# airball_sensor_board_v2.net
KiCad netlist of a schematic drawn in EAGLE
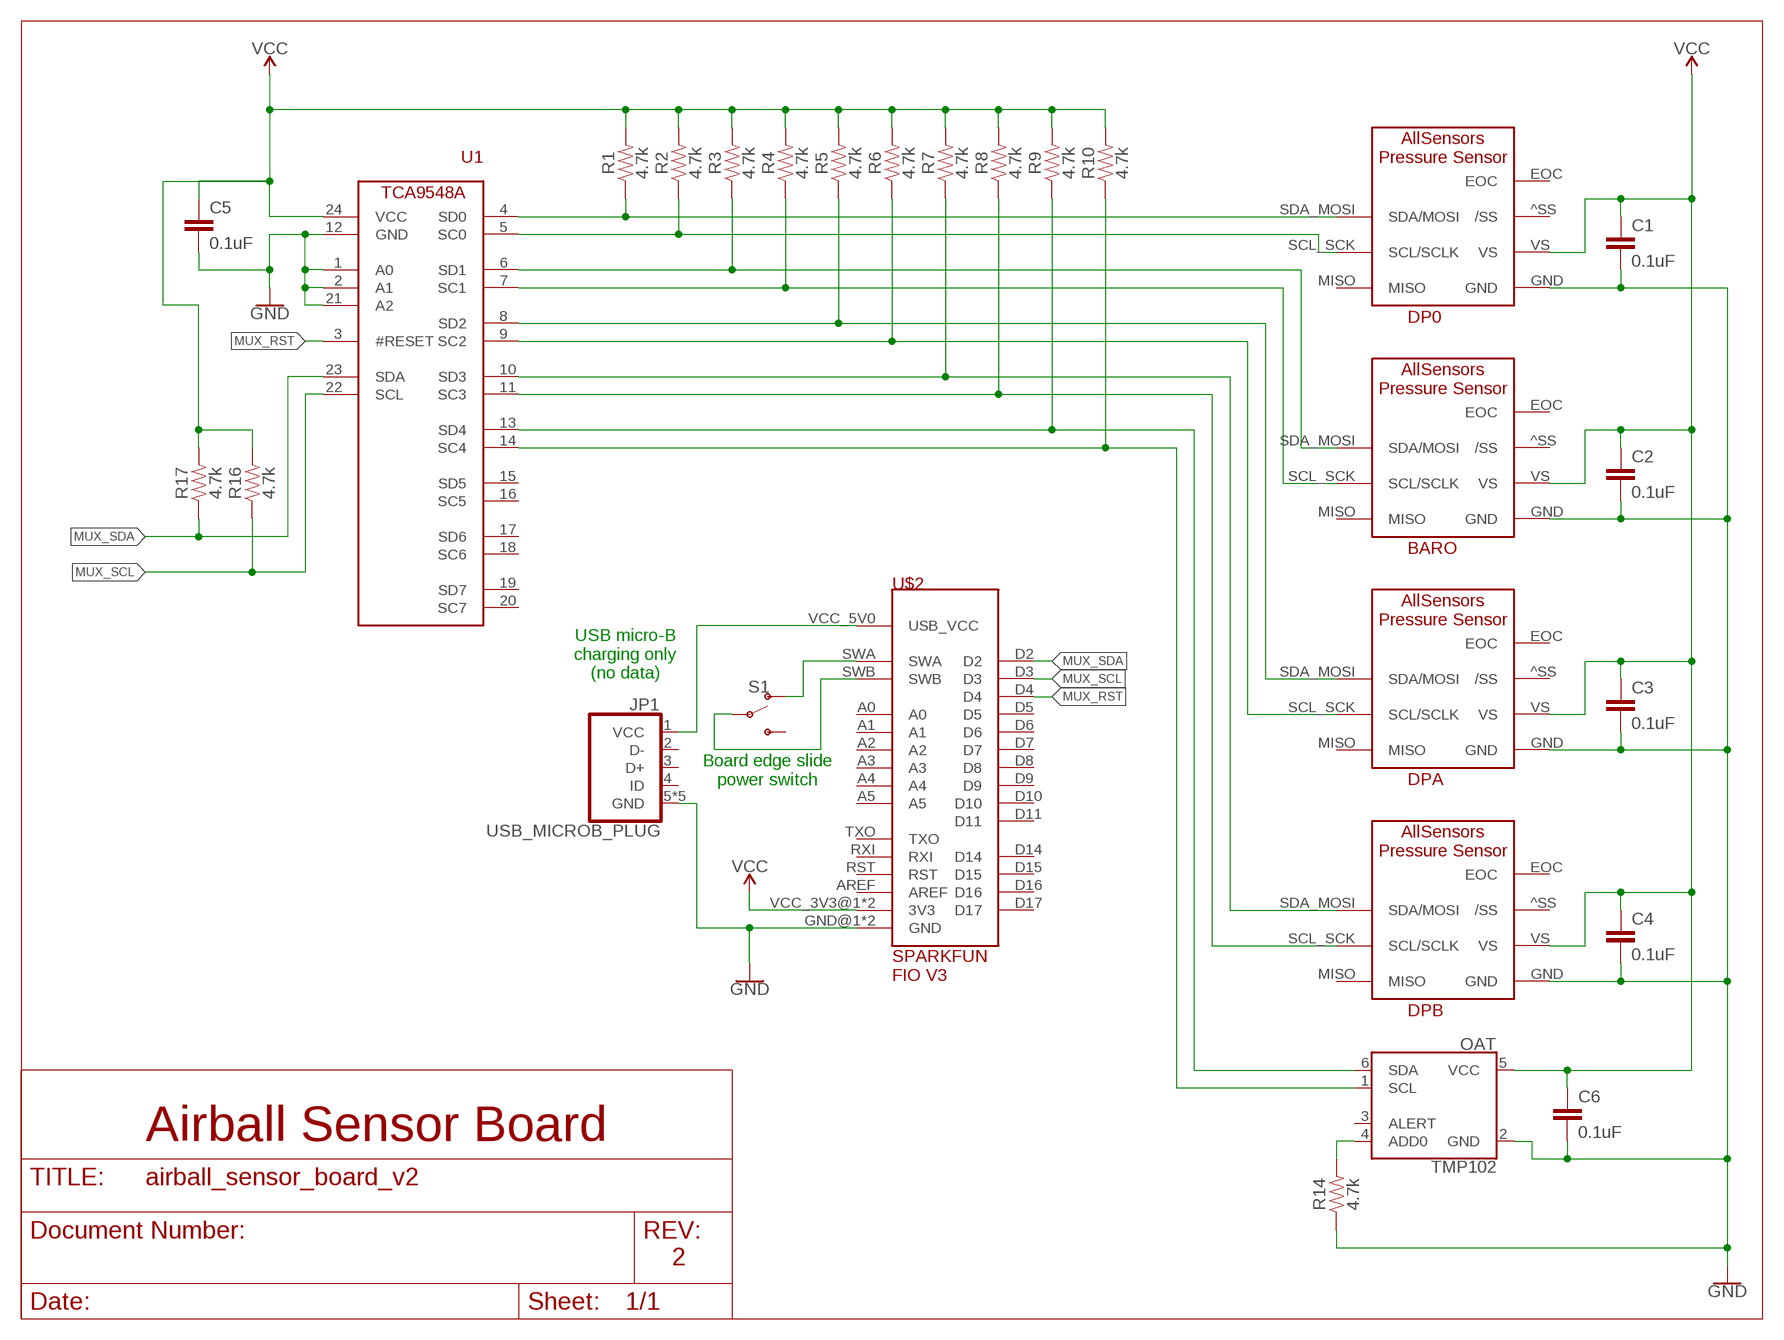
[diagram p0: schematic, sheet 1]

(export (version "E")
  (design (tool "Eeschema 10.0.6"))
  (components
    (comp (ref "BARO")
      (value "ALL_SENSORS_DLHR_E1ND")
      (footprint "eagle-import:ALL_SENSORS_E1BD_8PIN_THRU")
      (libsource (lib "eagle-import") (part "ALL_SENSORS_DLHR_E1ND"))
    )
    (comp (ref "C1")
      (value "0.1uF")
      (footprint "eagle-import:0603")
      (libsource (lib "eagle-import") (part "0.1UF-0603-25V-5%"))
    )
    (comp (ref "C2")
      (value "0.1uF")
      (footprint "eagle-import:0603")
      (libsource (lib "eagle-import") (part "0.1UF-0603-25V-5%"))
    )
    (comp (ref "C3")
      (value "0.1uF")
      (footprint "eagle-import:0603")
      (libsource (lib "eagle-import") (part "0.1UF-0603-25V-5%"))
    )
    (comp (ref "C4")
      (value "0.1uF")
      (footprint "eagle-import:0603")
      (libsource (lib "eagle-import") (part "0.1UF-0603-25V-5%"))
    )
    (comp (ref "C5")
      (value "0.1uF")
      (footprint "eagle-import:0603")
      (libsource (lib "eagle-import") (part "0.1UF-0603-25V-5%"))
    )
    (comp (ref "C6")
      (value "0.1uF")
      (footprint "eagle-import:0603")
      (libsource (lib "eagle-import") (part "0.1UF-0603-25V-5%"))
    )
    (comp (ref "DP0")
      (value "ALL_SENSORS_DLHR_E1ND")
      (footprint "eagle-import:ALL_SENSORS_E1BD_8PIN_THRU")
      (libsource (lib "eagle-import") (part "ALL_SENSORS_DLHR_E1ND"))
    )
    (comp (ref "DPA")
      (value "ALL_SENSORS_DLHR_E1ND")
      (footprint "eagle-import:ALL_SENSORS_E1BD_8PIN_THRU")
      (libsource (lib "eagle-import") (part "ALL_SENSORS_DLHR_E1ND"))
    )
    (comp (ref "DPB")
      (value "ALL_SENSORS_DLHR_E1ND")
      (footprint "eagle-import:ALL_SENSORS_E1BD_8PIN_THRU")
      (libsource (lib "eagle-import") (part "ALL_SENSORS_DLHR_E1ND"))
    )
    (comp (ref "JP1")
      (value "USB_MICROB_PLUG")
      (footprint "eagle-import:USB_MICRO_B_TYCO")
      (libsource (lib "eagle-import") (part "USB_MICROB_PLUG"))
    )
    (comp (ref "OAT")
      (value "TMP102")
      (footprint "eagle-import:SOT563")
      (libsource (lib "eagle-import") (part "TMP102"))
    )
    (comp (ref "R1")
      (value "4.7k")
      (footprint "eagle-import:0603")
      (libsource (lib "eagle-import") (part "4.7KOHM-0603-1/10W-1%"))
    )
    (comp (ref "R2")
      (value "4.7k")
      (footprint "eagle-import:0603")
      (libsource (lib "eagle-import") (part "4.7KOHM-0603-1/10W-1%"))
    )
    (comp (ref "R3")
      (value "4.7k")
      (footprint "eagle-import:0603")
      (libsource (lib "eagle-import") (part "4.7KOHM-0603-1/10W-1%"))
    )
    (comp (ref "R4")
      (value "4.7k")
      (footprint "eagle-import:0603")
      (libsource (lib "eagle-import") (part "4.7KOHM-0603-1/10W-1%"))
    )
    (comp (ref "R5")
      (value "4.7k")
      (footprint "eagle-import:0603")
      (libsource (lib "eagle-import") (part "4.7KOHM-0603-1/10W-1%"))
    )
    (comp (ref "R6")
      (value "4.7k")
      (footprint "eagle-import:0603")
      (libsource (lib "eagle-import") (part "4.7KOHM-0603-1/10W-1%"))
    )
    (comp (ref "R7")
      (value "4.7k")
      (footprint "eagle-import:0603")
      (libsource (lib "eagle-import") (part "4.7KOHM-0603-1/10W-1%"))
    )
    (comp (ref "R8")
      (value "4.7k")
      (footprint "eagle-import:0603")
      (libsource (lib "eagle-import") (part "4.7KOHM-0603-1/10W-1%"))
    )
    (comp (ref "R9")
      (value "4.7k")
      (footprint "eagle-import:0603")
      (libsource (lib "eagle-import") (part "4.7KOHM-0603-1/10W-1%"))
    )
    (comp (ref "R10")
      (value "4.7k")
      (footprint "eagle-import:0603")
      (libsource (lib "eagle-import") (part "4.7KOHM-0603-1/10W-1%"))
    )
    (comp (ref "R14")
      (value "4.7k")
      (footprint "eagle-import:0603")
      (libsource (lib "eagle-import") (part "4.7KOHM-0603-1/10W-1%"))
    )
    (comp (ref "R16")
      (value "4.7k")
      (footprint "eagle-import:0603")
      (libsource (lib "eagle-import") (part "4.7KOHM-0603-1/10W-1%"))
    )
    (comp (ref "R17")
      (value "4.7k")
      (footprint "eagle-import:0603")
      (libsource (lib "eagle-import") (part "4.7KOHM-0603-1/10W-1%"))
    )
    (comp (ref "S1")
      (value "SWITCH-SPDT-SMD-RIGHT-ANGLE")
      (footprint "eagle-import:SWITCH_SPST_SMD_A")
      (libsource (lib "eagle-import") (part "SWITCH-SPDT-SMD-RIGHT-ANGLE"))
    )
    (comp (ref "U$2")
      (value "SPARKFUN_FIO_V3")
      (footprint "eagle-import:SPARKFUN_FIO_V3")
      (libsource (lib "eagle-import") (part "SPARKFUN_FIO_V3"))
    )
    (comp (ref "U1")
      (value "TCA9548ATSSOP24")
      (footprint "eagle-import:TSSOP24")
      (libsource (lib "eagle-import") (part "TCA9548ATSSOP24"))
    )
  )
  (nets
    (net (code "1") (name "GND") (class "Default")
      (node (ref "BARO") (pin "GND") (pinfunction "GND_GND") (pintype "power_in"))
      (node (ref "C1") (pin "2") (pinfunction "2_2") (pintype "passive"))
      (node (ref "C2") (pin "2") (pinfunction "2_2") (pintype "passive"))
      (node (ref "C3") (pin "2") (pinfunction "2_2") (pintype "passive"))
      (node (ref "C4") (pin "2") (pinfunction "2_2") (pintype "passive"))
      (node (ref "C5") (pin "2") (pinfunction "2_2") (pintype "passive"))
      (node (ref "C6") (pin "2") (pinfunction "2_2") (pintype "passive"))
      (node (ref "DP0") (pin "GND") (pinfunction "GND_GND") (pintype "power_in"))
      (node (ref "DPA") (pin "GND") (pinfunction "GND_GND") (pintype "power_in"))
      (node (ref "DPB") (pin "GND") (pinfunction "GND_GND") (pintype "power_in"))
      (node (ref "JP1") (pin "5") (pinfunction "GND_5") (pintype "bidirectional"))
      (node (ref "JP1") (pin "SH@1") (pinfunction "GND_SH@1") (pintype "bidirectional"))
      (node (ref "JP1") (pin "SH@2") (pinfunction "GND_SH@2") (pintype "bidirectional"))
      (node (ref "JP1") (pin "SH@3") (pinfunction "GND_SH@3") (pintype "bidirectional"))
      (node (ref "JP1") (pin "SH@4") (pinfunction "GND_SH@4") (pintype "bidirectional"))
      (node (ref "OAT") (pin "2") (pinfunction "GND_2") (pintype "bidirectional"))
      (node (ref "R14") (pin "1") (pinfunction "1_1") (pintype "passive"))
      (node (ref "U$2") (pin "GND@1") (pinfunction "GND_GND@1") (pintype "power_in"))
      (node (ref "U$2") (pin "GND@2") (pinfunction "GND_GND@2") (pintype "power_in"))
      (node (ref "U1") (pin "1") (pinfunction "A0_1") (pintype "bidirectional"))
      (node (ref "U1") (pin "12") (pinfunction "GND_12") (pintype "bidirectional"))
      (node (ref "U1") (pin "2") (pinfunction "A1_2") (pintype "bidirectional"))
      (node (ref "U1") (pin "21") (pinfunction "A2_21") (pintype "bidirectional"))
    )
    (net (code "2") (name "MUX_RST") (class "Default")
      (node (ref "U$2") (pin "D4") (pinfunction "D4_D4") (pintype "bidirectional"))
      (node (ref "U1") (pin "3") (pinfunction "#RESET_3") (pintype "bidirectional"))
    )
    (net (code "3") (name "MUX_SCL") (class "Default")
      (node (ref "R16") (pin "1") (pinfunction "1_1") (pintype "passive"))
      (node (ref "U$2") (pin "D3") (pinfunction "D3_D3") (pintype "bidirectional"))
      (node (ref "U1") (pin "22") (pinfunction "SCL_22") (pintype "bidirectional"))
    )
    (net (code "4") (name "MUX_SDA") (class "Default")
      (node (ref "R17") (pin "1") (pinfunction "1_1") (pintype "passive"))
      (node (ref "U$2") (pin "D2") (pinfunction "D2_D2") (pintype "bidirectional"))
      (node (ref "U1") (pin "23") (pinfunction "SDA_23") (pintype "bidirectional"))
    )
    (net (code "5") (name "Net-(BARO-SCL{slash}SCLK)") (class "Default")
      (node (ref "BARO") (pin "SCL_SCK") (pinfunction "SCL/SCLK_SCL_SCK") (pintype "bidirectional"))
      (node (ref "R4") (pin "1") (pinfunction "1_1") (pintype "passive"))
      (node (ref "U1") (pin "7") (pinfunction "SC1_7") (pintype "bidirectional"))
    )
    (net (code "6") (name "Net-(BARO-SDA{slash}MOSI)") (class "Default")
      (node (ref "BARO") (pin "SDA_MOSI") (pinfunction "SDA/MOSI_SDA_MOSI") (pintype "bidirectional"))
      (node (ref "R3") (pin "1") (pinfunction "1_1") (pintype "passive"))
      (node (ref "U1") (pin "6") (pinfunction "SD1_6") (pintype "bidirectional"))
    )
    (net (code "7") (name "Net-(DP0-SCL{slash}SCLK)") (class "Default")
      (node (ref "DP0") (pin "SCL_SCK") (pinfunction "SCL/SCLK_SCL_SCK") (pintype "bidirectional"))
      (node (ref "R2") (pin "1") (pinfunction "1_1") (pintype "passive"))
      (node (ref "U1") (pin "5") (pinfunction "SC0_5") (pintype "bidirectional"))
    )
    (net (code "8") (name "Net-(DP0-SDA{slash}MOSI)") (class "Default")
      (node (ref "DP0") (pin "SDA_MOSI") (pinfunction "SDA/MOSI_SDA_MOSI") (pintype "bidirectional"))
      (node (ref "R1") (pin "1") (pinfunction "1_1") (pintype "passive"))
      (node (ref "U1") (pin "4") (pinfunction "SD0_4") (pintype "bidirectional"))
    )
    (net (code "9") (name "Net-(DPA-SCL{slash}SCLK)") (class "Default")
      (node (ref "DPA") (pin "SCL_SCK") (pinfunction "SCL/SCLK_SCL_SCK") (pintype "bidirectional"))
      (node (ref "R6") (pin "1") (pinfunction "1_1") (pintype "passive"))
      (node (ref "U1") (pin "9") (pinfunction "SC2_9") (pintype "bidirectional"))
    )
    (net (code "10") (name "Net-(DPA-SDA{slash}MOSI)") (class "Default")
      (node (ref "DPA") (pin "SDA_MOSI") (pinfunction "SDA/MOSI_SDA_MOSI") (pintype "bidirectional"))
      (node (ref "R5") (pin "1") (pinfunction "1_1") (pintype "passive"))
      (node (ref "U1") (pin "8") (pinfunction "SD2_8") (pintype "bidirectional"))
    )
    (net (code "11") (name "Net-(DPB-SCL{slash}SCLK)") (class "Default")
      (node (ref "DPB") (pin "SCL_SCK") (pinfunction "SCL/SCLK_SCL_SCK") (pintype "bidirectional"))
      (node (ref "R8") (pin "1") (pinfunction "1_1") (pintype "passive"))
      (node (ref "U1") (pin "11") (pinfunction "SC3_11") (pintype "bidirectional"))
    )
    (net (code "12") (name "Net-(DPB-SDA{slash}MOSI)") (class "Default")
      (node (ref "DPB") (pin "SDA_MOSI") (pinfunction "SDA/MOSI_SDA_MOSI") (pintype "bidirectional"))
      (node (ref "R7") (pin "1") (pinfunction "1_1") (pintype "passive"))
      (node (ref "U1") (pin "10") (pinfunction "SD3_10") (pintype "bidirectional"))
    )
    (net (code "13") (name "Net-(JP1-VCC)") (class "Default")
      (node (ref "JP1") (pin "1") (pinfunction "VCC_1") (pintype "bidirectional"))
      (node (ref "U$2") (pin "VCC_5V0") (pinfunction "USB_VCC_VCC_5V0") (pintype "power_in"))
    )
    (net (code "14") (name "Net-(OAT-ADD0)") (class "Default")
      (node (ref "OAT") (pin "4") (pinfunction "ADD0_4") (pintype "bidirectional"))
      (node (ref "R14") (pin "2") (pinfunction "2_2") (pintype "passive"))
    )
    (net (code "15") (name "Net-(OAT-SCL)") (class "Default")
      (node (ref "OAT") (pin "1") (pinfunction "SCL_1") (pintype "bidirectional"))
      (node (ref "R10") (pin "1") (pinfunction "1_1") (pintype "passive"))
      (node (ref "U1") (pin "14") (pinfunction "SC4_14") (pintype "bidirectional"))
    )
    (net (code "16") (name "Net-(OAT-SDA)") (class "Default")
      (node (ref "OAT") (pin "6") (pinfunction "SDA_6") (pintype "bidirectional"))
      (node (ref "R9") (pin "1") (pinfunction "1_1") (pintype "passive"))
      (node (ref "U1") (pin "13") (pinfunction "SD4_13") (pintype "bidirectional"))
    )
    (net (code "17") (name "Net-(S1-O)") (class "Default")
      (node (ref "S1") (pin "1") (pinfunction "O_1") (pintype "passive"))
      (node (ref "U$2") (pin "SWA") (pinfunction "SWA_SWA") (pintype "bidirectional"))
    )
    (net (code "18") (name "Net-(S1-P)") (class "Default")
      (node (ref "S1") (pin "2") (pinfunction "P_2") (pintype "passive"))
      (node (ref "U$2") (pin "SWB") (pinfunction "SWB_SWB") (pintype "bidirectional"))
    )
    (net (code "19") (name "VCC") (class "Default")
      (node (ref "BARO") (pin "VS") (pinfunction "VS_VS") (pintype "power_in"))
      (node (ref "C1") (pin "1") (pinfunction "1_1") (pintype "passive"))
      (node (ref "C2") (pin "1") (pinfunction "1_1") (pintype "passive"))
      (node (ref "C3") (pin "1") (pinfunction "1_1") (pintype "passive"))
      (node (ref "C4") (pin "1") (pinfunction "1_1") (pintype "passive"))
      (node (ref "C5") (pin "1") (pinfunction "1_1") (pintype "passive"))
      (node (ref "C6") (pin "1") (pinfunction "1_1") (pintype "passive"))
      (node (ref "DP0") (pin "VS") (pinfunction "VS_VS") (pintype "power_in"))
      (node (ref "DPA") (pin "VS") (pinfunction "VS_VS") (pintype "power_in"))
      (node (ref "DPB") (pin "VS") (pinfunction "VS_VS") (pintype "power_in"))
      (node (ref "OAT") (pin "5") (pinfunction "VCC_5") (pintype "bidirectional"))
      (node (ref "R1") (pin "2") (pinfunction "2_2") (pintype "passive"))
      (node (ref "R10") (pin "2") (pinfunction "2_2") (pintype "passive"))
      (node (ref "R16") (pin "2") (pinfunction "2_2") (pintype "passive"))
      (node (ref "R17") (pin "2") (pinfunction "2_2") (pintype "passive"))
      (node (ref "R2") (pin "2") (pinfunction "2_2") (pintype "passive"))
      (node (ref "R3") (pin "2") (pinfunction "2_2") (pintype "passive"))
      (node (ref "R4") (pin "2") (pinfunction "2_2") (pintype "passive"))
      (node (ref "R5") (pin "2") (pinfunction "2_2") (pintype "passive"))
      (node (ref "R6") (pin "2") (pinfunction "2_2") (pintype "passive"))
      (node (ref "R7") (pin "2") (pinfunction "2_2") (pintype "passive"))
      (node (ref "R8") (pin "2") (pinfunction "2_2") (pintype "passive"))
      (node (ref "R9") (pin "2") (pinfunction "2_2") (pintype "passive"))
      (node (ref "U$2") (pin "VCC_3V3@1") (pinfunction "3V3_VCC_3V3@1") (pintype "power_in"))
      (node (ref "U$2") (pin "VCC_3V3@2") (pinfunction "3V3_VCC_3V3@2") (pintype "power_in"))
      (node (ref "U1") (pin "24") (pinfunction "VCC_24") (pintype "bidirectional"))
    )
    (net (code "20") (name "unconnected-(BARO-PadEOC)") (class "Default")
      (node (ref "BARO") (pin "EOC") (pinfunction "EOC_EOC") (pintype "bidirectional"))
    )
    (net (code "21") (name "unconnected-(BARO-PadMISO)") (class "Default")
      (node (ref "BARO") (pin "MISO") (pinfunction "MISO_MISO") (pintype "input"))
    )
    (net (code "22") (name "unconnected-(BARO-{slash}SS-Pad^SS)") (class "Default")
      (node (ref "BARO") (pin "^SS") (pinfunction "/SS_^SS") (pintype "input"))
    )
    (net (code "23") (name "unconnected-(DP0-PadEOC)") (class "Default")
      (node (ref "DP0") (pin "EOC") (pinfunction "EOC_EOC") (pintype "bidirectional"))
    )
    (net (code "24") (name "unconnected-(DP0-PadMISO)") (class "Default")
      (node (ref "DP0") (pin "MISO") (pinfunction "MISO_MISO") (pintype "input"))
    )
    (net (code "25") (name "unconnected-(DP0-{slash}SS-Pad^SS)") (class "Default")
      (node (ref "DP0") (pin "^SS") (pinfunction "/SS_^SS") (pintype "input"))
    )
    (net (code "26") (name "unconnected-(DPA-PadEOC)") (class "Default")
      (node (ref "DPA") (pin "EOC") (pinfunction "EOC_EOC") (pintype "bidirectional"))
    )
    (net (code "27") (name "unconnected-(DPA-PadMISO)") (class "Default")
      (node (ref "DPA") (pin "MISO") (pinfunction "MISO_MISO") (pintype "input"))
    )
    (net (code "28") (name "unconnected-(DPA-{slash}SS-Pad^SS)") (class "Default")
      (node (ref "DPA") (pin "^SS") (pinfunction "/SS_^SS") (pintype "input"))
    )
    (net (code "29") (name "unconnected-(DPB-PadEOC)") (class "Default")
      (node (ref "DPB") (pin "EOC") (pinfunction "EOC_EOC") (pintype "bidirectional"))
    )
    (net (code "30") (name "unconnected-(DPB-PadMISO)") (class "Default")
      (node (ref "DPB") (pin "MISO") (pinfunction "MISO_MISO") (pintype "input"))
    )
    (net (code "31") (name "unconnected-(DPB-{slash}SS-Pad^SS)") (class "Default")
      (node (ref "DPB") (pin "^SS") (pinfunction "/SS_^SS") (pintype "input"))
    )
    (net (code "32") (name "unconnected-(JP1-D+-Pad3)") (class "Default")
      (node (ref "JP1") (pin "3") (pinfunction "D+_3") (pintype "bidirectional"))
    )
    (net (code "33") (name "unconnected-(JP1-D--Pad2)") (class "Default")
      (node (ref "JP1") (pin "2") (pinfunction "D-_2") (pintype "bidirectional"))
    )
    (net (code "34") (name "unconnected-(JP1-ID-Pad4)") (class "Default")
      (node (ref "JP1") (pin "4") (pinfunction "ID_4") (pintype "bidirectional"))
    )
    (net (code "35") (name "unconnected-(OAT-ALERT-Pad3)") (class "Default")
      (node (ref "OAT") (pin "3") (pinfunction "ALERT_3") (pintype "bidirectional"))
    )
    (net (code "36") (name "unconnected-(S1-S-Pad3)") (class "Default")
      (node (ref "S1") (pin "3") (pinfunction "S_3") (pintype "passive"))
    )
    (net (code "37") (name "unconnected-(U$2-PadA0)") (class "Default")
      (node (ref "U$2") (pin "A0") (pinfunction "A0_A0") (pintype "bidirectional"))
    )
    (net (code "38") (name "unconnected-(U$2-PadA1)") (class "Default")
      (node (ref "U$2") (pin "A1") (pinfunction "A1_A1") (pintype "bidirectional"))
    )
    (net (code "39") (name "unconnected-(U$2-PadA2)") (class "Default")
      (node (ref "U$2") (pin "A2") (pinfunction "A2_A2") (pintype "bidirectional"))
    )
    (net (code "40") (name "unconnected-(U$2-PadA3)") (class "Default")
      (node (ref "U$2") (pin "A3") (pinfunction "A3_A3") (pintype "bidirectional"))
    )
    (net (code "41") (name "unconnected-(U$2-PadA4)") (class "Default")
      (node (ref "U$2") (pin "A4") (pinfunction "A4_A4") (pintype "bidirectional"))
    )
    (net (code "42") (name "unconnected-(U$2-PadA5)") (class "Default")
      (node (ref "U$2") (pin "A5") (pinfunction "A5_A5") (pintype "bidirectional"))
    )
    (net (code "43") (name "unconnected-(U$2-PadAREF)") (class "Default")
      (node (ref "U$2") (pin "AREF") (pinfunction "AREF_AREF") (pintype "bidirectional"))
    )
    (net (code "44") (name "unconnected-(U$2-PadD5)") (class "Default")
      (node (ref "U$2") (pin "D5") (pinfunction "D5_D5") (pintype "bidirectional"))
    )
    (net (code "45") (name "unconnected-(U$2-PadD6)") (class "Default")
      (node (ref "U$2") (pin "D6") (pinfunction "D6_D6") (pintype "bidirectional"))
    )
    (net (code "46") (name "unconnected-(U$2-PadD7)") (class "Default")
      (node (ref "U$2") (pin "D7") (pinfunction "D7_D7") (pintype "bidirectional"))
    )
    (net (code "47") (name "unconnected-(U$2-PadD8)") (class "Default")
      (node (ref "U$2") (pin "D8") (pinfunction "D8_D8") (pintype "bidirectional"))
    )
    (net (code "48") (name "unconnected-(U$2-PadD9)") (class "Default")
      (node (ref "U$2") (pin "D9") (pinfunction "D9_D9") (pintype "bidirectional"))
    )
    (net (code "49") (name "unconnected-(U$2-PadD10)") (class "Default")
      (node (ref "U$2") (pin "D10") (pinfunction "D10_D10") (pintype "bidirectional"))
    )
    (net (code "50") (name "unconnected-(U$2-PadD11)") (class "Default")
      (node (ref "U$2") (pin "D11") (pinfunction "D11_D11") (pintype "bidirectional"))
    )
    (net (code "51") (name "unconnected-(U$2-PadD14)") (class "Default")
      (node (ref "U$2") (pin "D14") (pinfunction "D14_D14") (pintype "bidirectional"))
    )
    (net (code "52") (name "unconnected-(U$2-PadD15)") (class "Default")
      (node (ref "U$2") (pin "D15") (pinfunction "D15_D15") (pintype "bidirectional"))
    )
    (net (code "53") (name "unconnected-(U$2-PadD16)") (class "Default")
      (node (ref "U$2") (pin "D16") (pinfunction "D16_D16") (pintype "bidirectional"))
    )
    (net (code "54") (name "unconnected-(U$2-PadD17)") (class "Default")
      (node (ref "U$2") (pin "D17") (pinfunction "D17_D17") (pintype "bidirectional"))
    )
    (net (code "55") (name "unconnected-(U$2-PadRST)") (class "Default")
      (node (ref "U$2") (pin "RST") (pinfunction "RST_RST") (pintype "bidirectional"))
    )
    (net (code "56") (name "unconnected-(U$2-PadRXI)") (class "Default")
      (node (ref "U$2") (pin "RXI") (pinfunction "RXI_RXI") (pintype "input"))
    )
    (net (code "57") (name "unconnected-(U$2-PadTXO)") (class "Default")
      (node (ref "U$2") (pin "TXO") (pinfunction "TXO_TXO") (pintype "output"))
    )
    (net (code "58") (name "unconnected-(U1-SC5-Pad16)") (class "Default")
      (node (ref "U1") (pin "16") (pinfunction "SC5_16") (pintype "bidirectional"))
    )
    (net (code "59") (name "unconnected-(U1-SC6-Pad18)") (class "Default")
      (node (ref "U1") (pin "18") (pinfunction "SC6_18") (pintype "bidirectional"))
    )
    (net (code "60") (name "unconnected-(U1-SC7-Pad20)") (class "Default")
      (node (ref "U1") (pin "20") (pinfunction "SC7_20") (pintype "bidirectional"))
    )
    (net (code "61") (name "unconnected-(U1-SD5-Pad15)") (class "Default")
      (node (ref "U1") (pin "15") (pinfunction "SD5_15") (pintype "bidirectional"))
    )
    (net (code "62") (name "unconnected-(U1-SD6-Pad17)") (class "Default")
      (node (ref "U1") (pin "17") (pinfunction "SD6_17") (pintype "bidirectional"))
    )
    (net (code "63") (name "unconnected-(U1-SD7-Pad19)") (class "Default")
      (node (ref "U1") (pin "19") (pinfunction "SD7_19") (pintype "bidirectional"))
    )
  )
)
